# can.net
KiCad netlist of a schematic drawn in Altium Designer
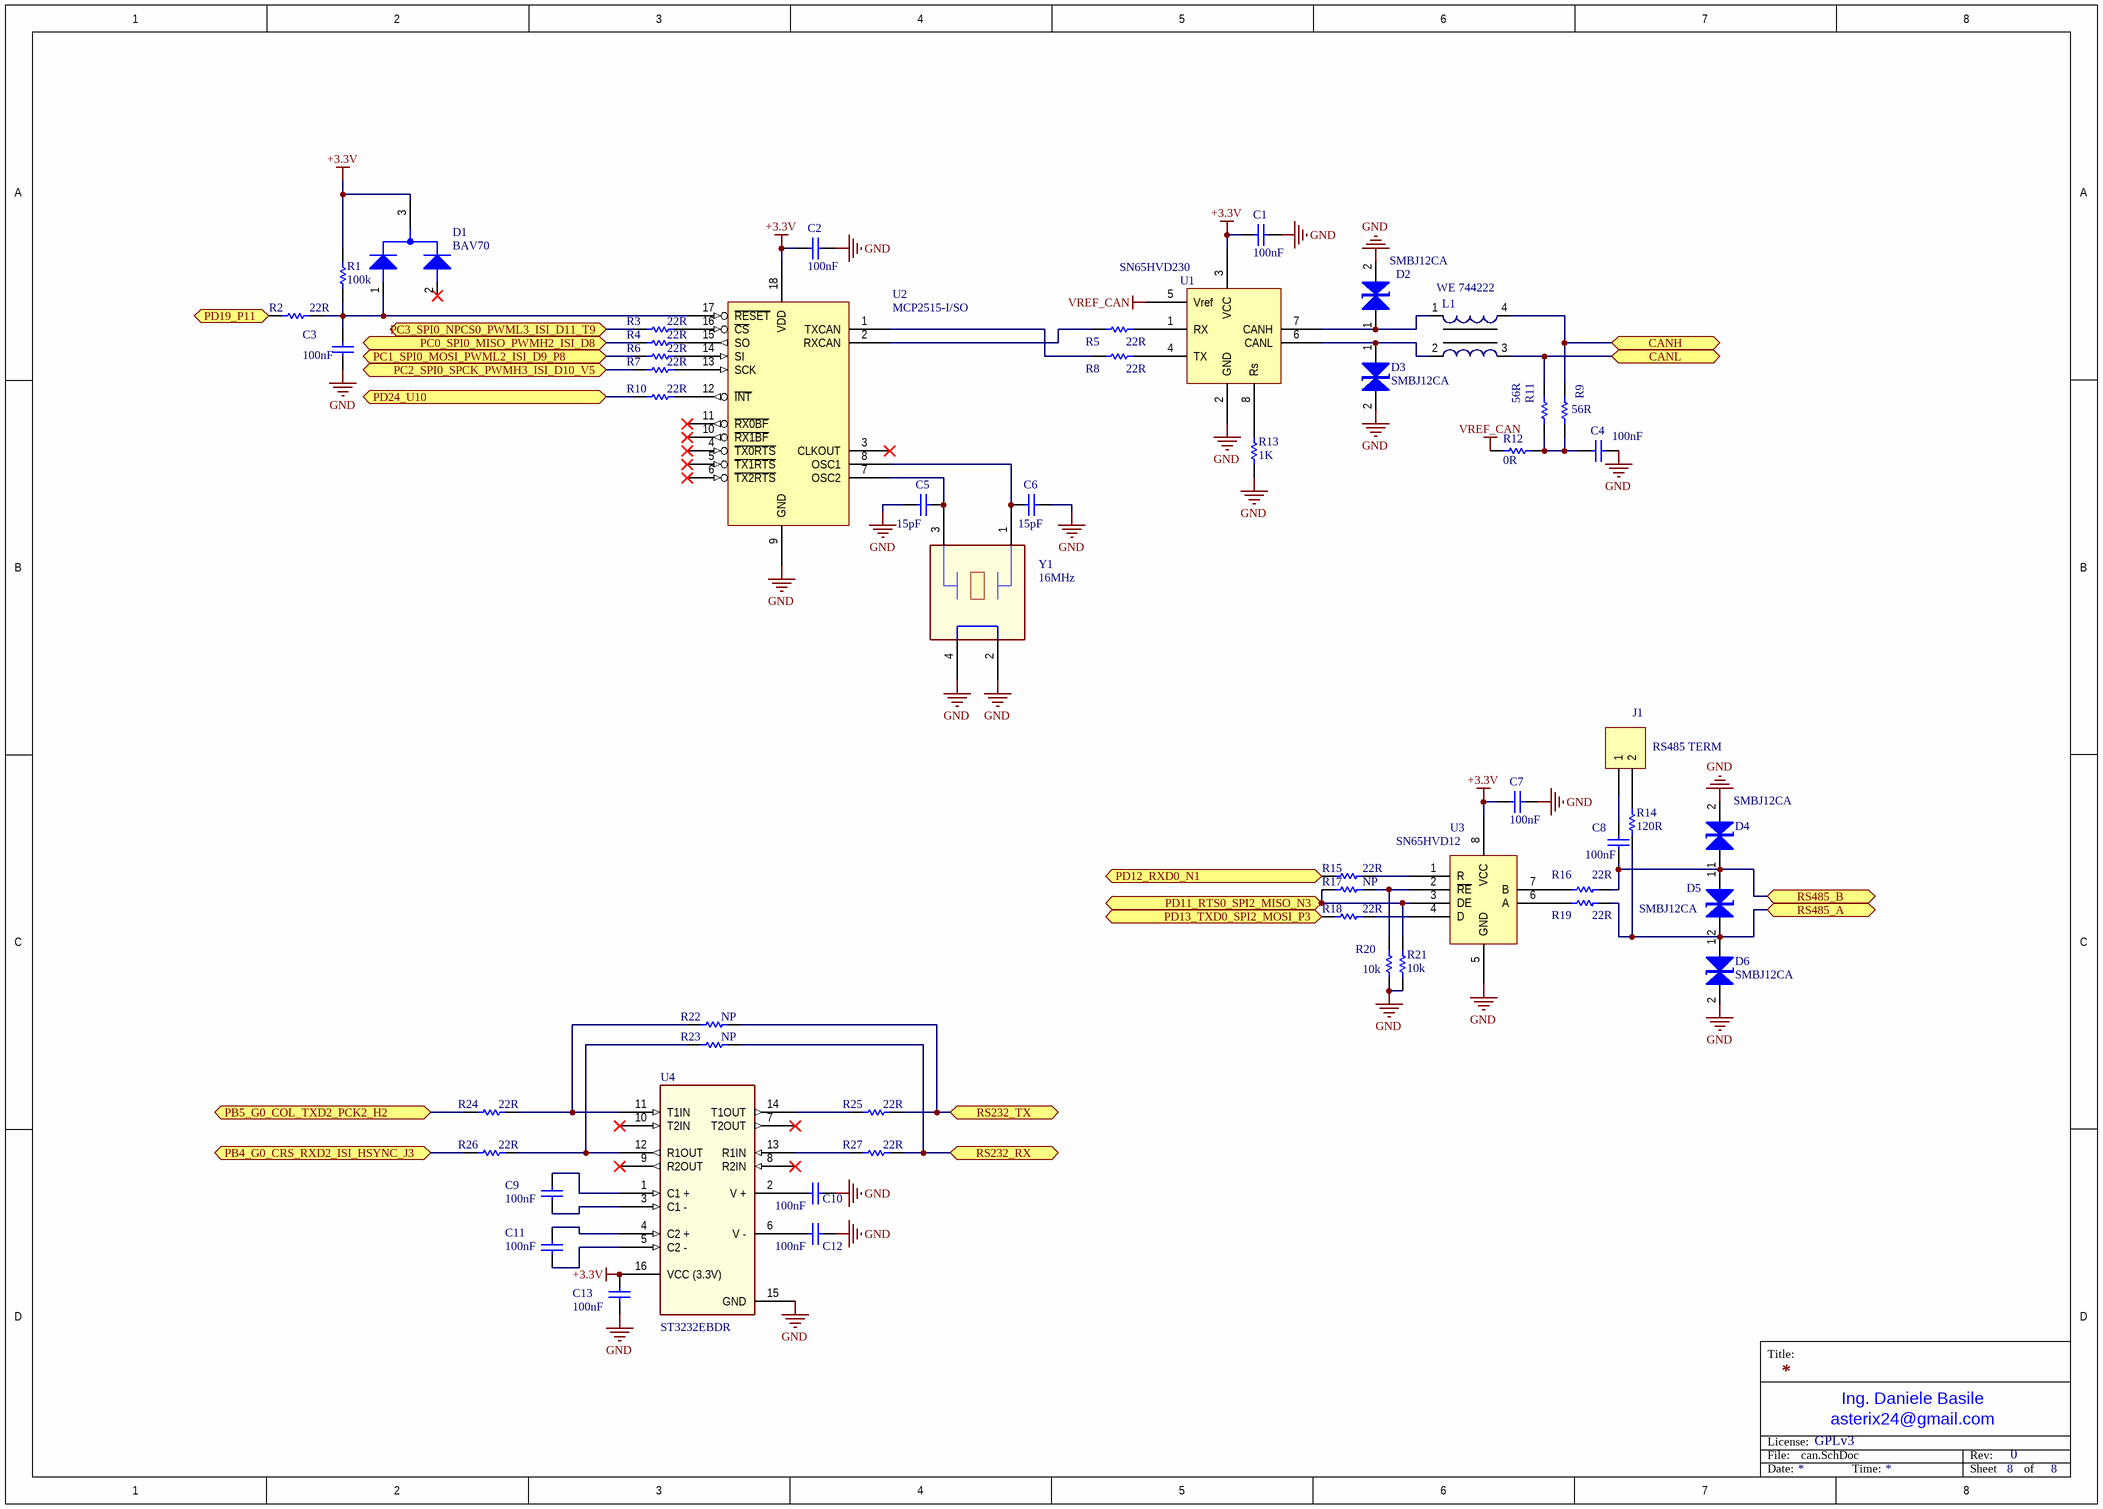
[diagram p0: can.SchDoc]

(export (version "E")
  (design (tool "Eeschema 10.0.6"))
  (components
    (comp (ref "C1")
      (value "100nF")
      (footprint "0603_[1608]")
      (description "Ceramic X7R 50V")
      (fields (field (name "PUBLISHER") "Altium Limited"))
      (libsource (lib "Miscellaneous Devices") (part "Cap"))
    )
    (comp (ref "C2")
      (value "100nF")
      (footprint "0603_[1608]")
      (description "Ceramic X7R 50V")
      (fields (field (name "PUBLISHER") "Altium Limited"))
      (libsource (lib "Miscellaneous Devices") (part "Cap"))
    )
    (comp (ref "C3")
      (value "100nF")
      (footprint "0603_[1608]")
      (description "Ceramic X7R 50V")
      (fields (field (name "PUBLISHER") "Altium Limited"))
      (libsource (lib "Miscellaneous Devices") (part "Cap"))
    )
    (comp (ref "C4")
      (value "100nF")
      (footprint "0603_[1608]")
      (description "Ceramic X7R 50V")
      (fields (field (name "PUBLISHER") "Altium Limited"))
      (libsource (lib "Miscellaneous Devices") (part "Cap"))
    )
    (comp (ref "C5")
      (value "15pF")
      (footprint "0603_[1608]")
      (description "Ceramic 50V NP0/C0G")
      (fields (field (name "PUBLISHER") "Altium Limited"))
      (libsource (lib "Miscellaneous Devices") (part "Cap"))
    )
    (comp (ref "C6")
      (value "15pF")
      (footprint "0603_[1608]")
      (description "Ceramic 50V NP0/C0G")
      (fields (field (name "PUBLISHER") "Altium Limited"))
      (libsource (lib "Miscellaneous Devices") (part "Cap"))
    )
    (comp (ref "C7")
      (value "100nF")
      (footprint "0603_[1608]")
      (description "Ceramic X7R 50V")
      (fields (field (name "PUBLISHER") "Altium Limited"))
      (libsource (lib "Miscellaneous Devices") (part "Cap"))
    )
    (comp (ref "C8")
      (value "100nF")
      (footprint "0603_[1608]")
      (description "Ceramic X7R 50V")
      (fields (field (name "PUBLISHER") "Altium Limited"))
      (libsource (lib "Miscellaneous Devices") (part "Cap"))
    )
    (comp (ref "C9")
      (value "100nF")
      (footprint "0603_[1608]")
      (description "Ceramic X7R 50V")
      (fields (field (name "PUBLISHER") "Altium Limited"))
      (libsource (lib "Miscellaneous Devices") (part "Cap"))
    )
    (comp (ref "C10")
      (value "100nF")
      (footprint "0603_[1608]")
      (description "Ceramic X7R 50V")
      (fields (field (name "PUBLISHER") "Altium Limited"))
      (libsource (lib "Miscellaneous Devices") (part "Cap"))
    )
    (comp (ref "C11")
      (value "100nF")
      (footprint "0603_[1608]")
      (description "Ceramic X7R 50V")
      (fields (field (name "PUBLISHER") "Altium Limited"))
      (libsource (lib "Miscellaneous Devices") (part "Cap"))
    )
    (comp (ref "C12")
      (value "100nF")
      (footprint "0603_[1608]")
      (description "Ceramic X7R 50V")
      (fields (field (name "PUBLISHER") "Altium Limited"))
      (libsource (lib "Miscellaneous Devices") (part "Cap"))
    )
    (comp (ref "C13")
      (value "100nF")
      (footprint "0603_[1608]")
      (description "Ceramic X7R 50V")
      (fields (field (name "PUBLISHER") "Altium Limited"))
      (libsource (lib "Miscellaneous Devices") (part "Cap"))
    )
    (comp (ref "D1")
      (value "BAV70")
      (footprint "SOT-23")
      (description "Diode")
      (libsource (lib "DEVELER_Library") (part "BAV70"))
    )
    (comp (ref "D2")
      (value "SMBJ12CA")
      (footprint "DO214AA_K1-A2_SMB")
      (description "TVS bidirectional")
      (libsource (lib "DEVELER_Library") (part "TVS bi"))
    )
    (comp (ref "D3")
      (value "SMBJ12CA")
      (footprint "DO214AA_K1-A2_SMB")
      (description "TVS bidirectional")
      (libsource (lib "DEVELER_Library") (part "TVS bi"))
    )
    (comp (ref "D4")
      (value "SMBJ12CA")
      (footprint "DO214AA_K1-A2_SMB")
      (description "TVS bidirectional")
      (libsource (lib "DEVELER_Library") (part "TVS bi"))
    )
    (comp (ref "D5")
      (value "SMBJ12CA")
      (footprint "DO214AA_K1-A2_SMB")
      (description "TVS bidirectional")
      (libsource (lib "DEVELER_Library") (part "TVS bi"))
    )
    (comp (ref "D6")
      (value "SMBJ12CA")
      (footprint "DO214AA_K1-A2_SMB")
      (description "TVS bidirectional")
      (libsource (lib "DEVELER_Library") (part "TVS bi"))
    )
    (comp (ref "J1")
      (value "RS485 TERM")
      (footprint "HEADER_1X2_2.54MM_THD")
      (description "Pin Header, 2.54mm, 1x2, 2pin")
      (fields (field (name "PUBLISHER") "Altium Limited"))
      (libsource (lib "Miscellaneous Connectors") (part "Header 2"))
    )
    (comp (ref "L1")
      (value "WE 744222")
      (footprint "WE-SL2")
      (description "Common Mode line Filter")
      (fields
        (field (name "PARTNO") "744821240")
        (field (name "MANUFACTURER") "Würth Elektronik eiSos GmbH")
        (field (name "CREATED BY") "Christin Zierenner")
      )
      (libsource (lib "DEVELER_Library") (part "WE-CMB XS, 744821240"))
    )
    (comp (ref "R1")
      (value "100k")
      (footprint "0603_[1608]")
      (description "Resistor")
      (libsource (lib "DEVELER_Library") (part "Res1"))
    )
    (comp (ref "R2")
      (value "22R")
      (footprint "0603_[1608]")
      (description "Resistor")
      (fields (field (name "PUBLISHER") "Altium Limited"))
      (libsource (lib "") (part "Res1_1"))
    )
    (comp (ref "R3")
      (value "22R")
      (footprint "0603_[1608]")
      (description "Resistor")
      (libsource (lib "DEVELER_Library") (part "Res1"))
    )
    (comp (ref "R4")
      (value "22R")
      (footprint "0603_[1608]")
      (description "Resistor")
      (libsource (lib "DEVELER_Library") (part "Res1"))
    )
    (comp (ref "R5")
      (value "22R")
      (footprint "0603_[1608]")
      (description "Resistor")
      (libsource (lib "DEVELER_Library") (part "Res1"))
    )
    (comp (ref "R6")
      (value "22R")
      (footprint "0603_[1608]")
      (description "Resistor")
      (libsource (lib "DEVELER_Library") (part "Res1"))
    )
    (comp (ref "R7")
      (value "22R")
      (footprint "0603_[1608]")
      (description "Resistor")
      (libsource (lib "DEVELER_Library") (part "Res1"))
    )
    (comp (ref "R8")
      (value "22R")
      (footprint "0603_[1608]")
      (description "Resistor")
      (libsource (lib "DEVELER_Library") (part "Res1"))
    )
    (comp (ref "R9")
      (value "56R")
      (footprint "0603_[1608]")
      (description "Resistor")
      (libsource (lib "DEVELER_Library") (part "Res1"))
    )
    (comp (ref "R10")
      (value "22R")
      (footprint "0603_[1608]")
      (description "Resistor")
      (libsource (lib "DEVELER_Library") (part "Res1"))
    )
    (comp (ref "R11")
      (value "56R")
      (footprint "0603_[1608]")
      (description "Resistor")
      (libsource (lib "DEVELER_Library") (part "Res1"))
    )
    (comp (ref "R12")
      (value "0R")
      (footprint "0603_[1608]")
      (description "Resistor")
      (libsource (lib "DEVELER_Library") (part "Res1"))
    )
    (comp (ref "R13")
      (value "1K")
      (footprint "0603_[1608]")
      (description "Resistor")
      (libsource (lib "DEVELER_Library") (part "Res1"))
    )
    (comp (ref "R14")
      (value "120R")
      (footprint "0603_[1608]")
      (description "Resistor")
      (libsource (lib "DEVELER_Library") (part "Res1"))
    )
    (comp (ref "R15")
      (value "22R")
      (footprint "0603_[1608]")
      (description "Resistor")
      (fields (field (name "PUBLISHER") "Altium Limited"))
      (libsource (lib "") (part "Res1_1"))
    )
    (comp (ref "R16")
      (value "22R")
      (footprint "0603_[1608]")
      (description "Resistor")
      (libsource (lib "DEVELER_Library") (part "Res1"))
    )
    (comp (ref "R17")
      (value "NP")
      (footprint "0603_[1608]")
      (description "Resistor")
      (libsource (lib "DEVELER_Library") (part "Res1"))
    )
    (comp (ref "R18")
      (value "22R")
      (footprint "0603_[1608]")
      (description "Resistor")
      (fields (field (name "PUBLISHER") "Altium Limited"))
      (libsource (lib "") (part "Res1_1"))
    )
    (comp (ref "R19")
      (value "22R")
      (footprint "0603_[1608]")
      (description "Resistor")
      (libsource (lib "DEVELER_Library") (part "Res1"))
    )
    (comp (ref "R20")
      (value "10k")
      (footprint "0603_[1608]")
      (description "Resistor")
      (libsource (lib "DEVELER_Library") (part "Res1"))
    )
    (comp (ref "R21")
      (value "10k")
      (footprint "0603_[1608]")
      (description "Resistor")
      (libsource (lib "DEVELER_Library") (part "Res1"))
    )
    (comp (ref "R22")
      (value "NP")
      (footprint "0603_[1608]")
      (description "Resistor")
      (libsource (lib "DEVELER_Library") (part "Res1"))
    )
    (comp (ref "R23")
      (value "NP")
      (footprint "0603_[1608]")
      (description "Resistor")
      (libsource (lib "DEVELER_Library") (part "Res1"))
    )
    (comp (ref "R24")
      (value "22R")
      (footprint "0603_[1608]")
      (description "Resistor")
      (libsource (lib "DEVELER_Library") (part "Res1"))
    )
    (comp (ref "R25")
      (value "22R")
      (footprint "0603_[1608]")
      (description "Resistor")
      (libsource (lib "DEVELER_Library") (part "Res1"))
    )
    (comp (ref "R26")
      (value "22R")
      (footprint "0603_[1608]")
      (description "Resistor")
      (libsource (lib "DEVELER_Library") (part "Res1"))
    )
    (comp (ref "R27")
      (value "22R")
      (footprint "0603_[1608]")
      (description "Resistor")
      (libsource (lib "DEVELER_Library") (part "Res1"))
    )
    (comp (ref "U1")
      (value "SN65HVD230")
      (footprint "SOIC8")
      (description "3.3V CAN bus transceiver (SN65HVD231; SN65HVD232)")
      (libsource (lib "DEVELER_Library") (part "SN65HVD230"))
    )
    (comp (ref "U2")
      (value "MCP2515-I/SO")
      (footprint "SOIC18")
      (description "Stand-Alone CAN controller with SPI interface")
      (libsource (lib "DEVELER_Library") (part "MCP2515"))
    )
    (comp (ref "U3")
      (value "SN65HVD12")
      (footprint "SOIC8")
      (description "3.3V to RS485 interface")
      (libsource (lib "DEVELER_Library") (part "SN65HVD12"))
    )
    (comp (ref "U4")
      (value "ST3232EBDR")
      (footprint "SOIC16")
      (description "3 to 5.5 V, low power, up to 400 kbps RS-232 driver")
      (fields (field (name "PART NUMBER") "STm ST3232CDR"))
      (libsource (lib "DEVELER_Library") (part "ST3232CDR"))
    )
    (comp (ref "Y1")
      (value "16MHz")
      (footprint "CRYSTAL_3.2X2.5MM_4P_SMD")
      (description "Crystal")
      (libsource (lib "DEVELER_Library") (part "CRYSTAL-4p"))
    )
  )
  (nets
    (net (code "1") (name "+3.3V") (class "Default")
      (node (ref "C1") (pin "2") (pinfunction "2_2") (pintype "passive"))
      (node (ref "C13") (pin "2") (pinfunction "2_2") (pintype "passive"))
      (node (ref "C2") (pin "2") (pinfunction "2_2") (pintype "passive"))
      (node (ref "C7") (pin "2") (pinfunction "2_2") (pintype "passive"))
      (node (ref "D1") (pin "3") (pinfunction "3_3") (pintype "passive"))
      (node (ref "R1") (pin "1") (pinfunction "1_1") (pintype "passive"))
      (node (ref "U1") (pin "3") (pinfunction "VCC_3") (pintype "power_in"))
      (node (ref "U2") (pin "18") (pinfunction "VDD_18") (pintype "power_in"))
      (node (ref "U3") (pin "8") (pinfunction "VCC_8") (pintype "power_in"))
      (node (ref "U4") (pin "16") (pinfunction "VCC_(3.3V)_16") (pintype "power_in"))
    )
    (net (code "2") (name "/CANH") (class "Default")
      (node (ref "L1") (pin "4") (pinfunction "4_4") (pintype "passive"))
      (node (ref "R9") (pin "1") (pinfunction "1_1") (pintype "passive"))
    )
    (net (code "3") (name "/CANL") (class "Default")
      (node (ref "L1") (pin "3") (pinfunction "3_3") (pintype "passive"))
      (node (ref "R11") (pin "1") (pinfunction "1_1") (pintype "passive"))
    )
    (net (code "4") (name "/PB4_G0_CRS_RXD2_ISI_HSYNC_J3") (class "Default")
      (node (ref "R26") (pin "1") (pinfunction "1_1") (pintype "passive"))
    )
    (net (code "5") (name "/PB5_G0_COL_TXD2_PCK2_H2") (class "Default")
      (node (ref "R24") (pin "1") (pinfunction "1_1") (pintype "passive"))
    )
    (net (code "6") (name "/PC0_SPI0_MISO_PWMH2_ISI_D8") (class "Default")
      (node (ref "R4") (pin "1") (pinfunction "1_1") (pintype "passive"))
    )
    (net (code "7") (name "/PC1_SPI0_MOSI_PWML2_ISI_D9_P8") (class "Default")
      (node (ref "R6") (pin "1") (pinfunction "1_1") (pintype "passive"))
    )
    (net (code "8") (name "/PC2_SPI0_SPCK_PWMH3_ISI_D10_V5") (class "Default")
      (node (ref "R7") (pin "1") (pinfunction "1_1") (pintype "passive"))
    )
    (net (code "9") (name "/PC3_SPI0_NPCS0_PWML3_ISI_D11_T9") (class "Default")
      (node (ref "R3") (pin "1") (pinfunction "1_1") (pintype "passive"))
    )
    (net (code "10") (name "/PD11_RTS0_SPI2_MISO_N3") (class "Default")
      (node (ref "R17") (pin "2") (pinfunction "2_2") (pintype "passive"))
      (node (ref "R21") (pin "2") (pinfunction "2_2") (pintype "passive"))
      (node (ref "U3") (pin "3") (pinfunction "DE_3") (pintype "passive"))
    )
    (net (code "11") (name "/PD12_RXD0_N1") (class "Default")
      (node (ref "R15") (pin "2") (pinfunction "2_2") (pintype "passive"))
    )
    (net (code "12") (name "/PD13_TXD0_SPI2_MOSI_P3") (class "Default")
      (node (ref "R18") (pin "2") (pinfunction "2_2") (pintype "passive"))
    )
    (net (code "13") (name "/PD19_P11") (class "Default")
      (node (ref "R2") (pin "2") (pinfunction "2_2") (pintype "passive"))
    )
    (net (code "14") (name "/PD24_U10") (class "Default")
      (node (ref "R10") (pin "1") (pinfunction "1_1") (pintype "passive"))
    )
    (net (code "15") (name "/RS232_RX") (class "Default")
      (node (ref "R23") (pin "2") (pinfunction "2_2") (pintype "passive"))
      (node (ref "R27") (pin "2") (pinfunction "2_2") (pintype "passive"))
    )
    (net (code "16") (name "/RS232_TX") (class "Default")
      (node (ref "R22") (pin "2") (pinfunction "2_2") (pintype "passive"))
      (node (ref "R25") (pin "2") (pinfunction "2_2") (pintype "passive"))
    )
    (net (code "17") (name "/RS485_A") (class "Default")
      (node (ref "D5") (pin "2") (pinfunction "2_2") (pintype "passive"))
      (node (ref "D6") (pin "1") (pinfunction "1_1") (pintype "passive"))
      (node (ref "R14") (pin "2") (pinfunction "2_2") (pintype "passive"))
      (node (ref "R19") (pin "2") (pinfunction "2_2") (pintype "passive"))
    )
    (net (code "18") (name "/RS485_B") (class "Default")
      (node (ref "C8") (pin "2") (pinfunction "2_2") (pintype "passive"))
      (node (ref "D4") (pin "1") (pinfunction "1_1") (pintype "passive"))
      (node (ref "D5") (pin "1") (pinfunction "1_1") (pintype "passive"))
      (node (ref "R16") (pin "2") (pinfunction "2_2") (pintype "passive"))
    )
    (net (code "19") (name "GND") (class "Default")
      (node (ref "C1") (pin "1") (pinfunction "1_1") (pintype "passive"))
      (node (ref "C10") (pin "1") (pinfunction "1_1") (pintype "passive"))
      (node (ref "C12") (pin "1") (pinfunction "1_1") (pintype "passive"))
      (node (ref "C13") (pin "1") (pinfunction "1_1") (pintype "passive"))
      (node (ref "C2") (pin "1") (pinfunction "1_1") (pintype "passive"))
      (node (ref "C3") (pin "2") (pinfunction "2_2") (pintype "passive"))
      (node (ref "C4") (pin "1") (pinfunction "1_1") (pintype "passive"))
      (node (ref "C5") (pin "2") (pinfunction "2_2") (pintype "passive"))
      (node (ref "C6") (pin "1") (pinfunction "1_1") (pintype "passive"))
      (node (ref "C7") (pin "1") (pinfunction "1_1") (pintype "passive"))
      (node (ref "D2") (pin "2") (pinfunction "2_2") (pintype "passive"))
      (node (ref "D3") (pin "2") (pinfunction "2_2") (pintype "passive"))
      (node (ref "D4") (pin "2") (pinfunction "2_2") (pintype "passive"))
      (node (ref "D6") (pin "2") (pinfunction "2_2") (pintype "passive"))
      (node (ref "R13") (pin "1") (pinfunction "1_1") (pintype "passive"))
      (node (ref "R20") (pin "1") (pinfunction "1_1") (pintype "passive"))
      (node (ref "R21") (pin "1") (pinfunction "1_1") (pintype "passive"))
      (node (ref "U1") (pin "2") (pinfunction "GND_2") (pintype "power_in"))
      (node (ref "U2") (pin "9") (pinfunction "GND_9") (pintype "power_in"))
      (node (ref "U3") (pin "5") (pinfunction "GND_5") (pintype "power_in"))
      (node (ref "U4") (pin "15") (pinfunction "GND_15") (pintype "power_in"))
      (node (ref "Y1") (pin "2") (pinfunction "2_2") (pintype "passive"))
      (node (ref "Y1") (pin "4") (pinfunction "4_4") (pintype "passive"))
    )
    (net (code "20") (name "Net-(C4-Pad2)") (class "Default")
      (node (ref "C4") (pin "2") (pinfunction "2_2") (pintype "passive"))
      (node (ref "R11") (pin "2") (pinfunction "2_2") (pintype "passive"))
      (node (ref "R12") (pin "2") (pinfunction "2_2") (pintype "passive"))
      (node (ref "R9") (pin "2") (pinfunction "2_2") (pintype "passive"))
    )
    (net (code "21") (name "Net-(C8-Pad1)") (class "Default")
      (node (ref "C8") (pin "1") (pinfunction "1_1") (pintype "passive"))
      (node (ref "J1") (pin "1") (pinfunction "1_1") (pintype "passive"))
    )
    (net (code "22") (name "Net-(J1-Pad2)") (class "Default")
      (node (ref "J1") (pin "2") (pinfunction "2_2") (pintype "passive"))
      (node (ref "R14") (pin "1") (pinfunction "1_1") (pintype "passive"))
    )
    (net (code "23") (name "Net-(U1-CANH)") (class "Default")
      (node (ref "D2") (pin "1") (pinfunction "1_1") (pintype "passive"))
      (node (ref "L1") (pin "1") (pinfunction "1_1") (pintype "passive"))
      (node (ref "U1") (pin "7") (pinfunction "CANH_7") (pintype "passive"))
    )
    (net (code "24") (name "Net-(U1-CANL)") (class "Default")
      (node (ref "D3") (pin "1") (pinfunction "1_1") (pintype "passive"))
      (node (ref "L1") (pin "2") (pinfunction "2_2") (pintype "passive"))
      (node (ref "U1") (pin "6") (pinfunction "CANL_6") (pintype "passive"))
    )
    (net (code "25") (name "Net-(U1-RX)") (class "Default")
      (node (ref "R5") (pin "2") (pinfunction "2_2") (pintype "passive"))
      (node (ref "U1") (pin "1") (pinfunction "RX_1") (pintype "passive"))
    )
    (net (code "26") (name "Net-(U1-Rs)") (class "Default")
      (node (ref "R13") (pin "2") (pinfunction "2_2") (pintype "passive"))
      (node (ref "U1") (pin "8") (pinfunction "Rs_8") (pintype "passive"))
    )
    (net (code "27") (name "Net-(U1-TX)") (class "Default")
      (node (ref "R8") (pin "2") (pinfunction "2_2") (pintype "passive"))
      (node (ref "U1") (pin "4") (pinfunction "TX_4") (pintype "passive"))
    )
    (net (code "28") (name "Net-(U2-OSC1)") (class "Default")
      (node (ref "C6") (pin "2") (pinfunction "2_2") (pintype "passive"))
      (node (ref "U2") (pin "8") (pinfunction "OSC1_8") (pintype "passive"))
      (node (ref "Y1") (pin "1") (pinfunction "1_1") (pintype "passive"))
    )
    (net (code "29") (name "Net-(U2-OSC2)") (class "Default")
      (node (ref "C5") (pin "1") (pinfunction "1_1") (pintype "passive"))
      (node (ref "U2") (pin "7") (pinfunction "OSC2_7") (pintype "passive"))
      (node (ref "Y1") (pin "3") (pinfunction "3_3") (pintype "passive"))
    )
    (net (code "30") (name "Net-(U2-RXCAN)") (class "Default")
      (node (ref "R5") (pin "1") (pinfunction "1_1") (pintype "passive"))
      (node (ref "U2") (pin "2") (pinfunction "RXCAN_2") (pintype "passive"))
    )
    (net (code "31") (name "Net-(U2-SCK)") (class "Default")
      (node (ref "R7") (pin "2") (pinfunction "2_2") (pintype "passive"))
      (node (ref "U2") (pin "13") (pinfunction "SCK_13") (pintype "input"))
    )
    (net (code "32") (name "Net-(U2-SI)") (class "Default")
      (node (ref "R6") (pin "2") (pinfunction "2_2") (pintype "passive"))
      (node (ref "U2") (pin "14") (pinfunction "SI_14") (pintype "input"))
    )
    (net (code "33") (name "Net-(U2-SO)") (class "Default")
      (node (ref "R4") (pin "2") (pinfunction "2_2") (pintype "passive"))
      (node (ref "U2") (pin "15") (pinfunction "SO_15") (pintype "output"))
    )
    (net (code "34") (name "Net-(U2-TXCAN)") (class "Default")
      (node (ref "R8") (pin "1") (pinfunction "1_1") (pintype "passive"))
      (node (ref "U2") (pin "1") (pinfunction "TXCAN_1") (pintype "passive"))
    )
    (net (code "35") (name "Net-(U2-~{CS})") (class "Default")
      (node (ref "R3") (pin "2") (pinfunction "2_2") (pintype "passive"))
      (node (ref "U2") (pin "16") (pinfunction "~{CS}_16") (pintype "input"))
    )
    (net (code "36") (name "Net-(U2-~{INT})") (class "Default")
      (node (ref "R10") (pin "2") (pinfunction "2_2") (pintype "passive"))
      (node (ref "U2") (pin "12") (pinfunction "~{INT}_12") (pintype "output"))
    )
    (net (code "37") (name "Net-(U2-~{RESET})") (class "Default")
      (node (ref "C3") (pin "1") (pinfunction "1_1") (pintype "passive"))
      (node (ref "D1") (pin "1") (pinfunction "1_1") (pintype "passive"))
      (node (ref "R1") (pin "2") (pinfunction "2_2") (pintype "passive"))
      (node (ref "R2") (pin "1") (pinfunction "1_1") (pintype "passive"))
      (node (ref "U2") (pin "17") (pinfunction "~{RESET}_17") (pintype "input"))
    )
    (net (code "38") (name "Net-(U3-A)") (class "Default")
      (node (ref "R19") (pin "1") (pinfunction "1_1") (pintype "passive"))
      (node (ref "U3") (pin "6") (pinfunction "A_6") (pintype "passive"))
    )
    (net (code "39") (name "Net-(U3-B)") (class "Default")
      (node (ref "R16") (pin "1") (pinfunction "1_1") (pintype "passive"))
      (node (ref "U3") (pin "7") (pinfunction "B_7") (pintype "passive"))
    )
    (net (code "40") (name "Net-(U3-D)") (class "Default")
      (node (ref "R18") (pin "1") (pinfunction "1_1") (pintype "passive"))
      (node (ref "U3") (pin "4") (pinfunction "D_4") (pintype "passive"))
    )
    (net (code "41") (name "Net-(U3-R)") (class "Default")
      (node (ref "R15") (pin "1") (pinfunction "1_1") (pintype "passive"))
      (node (ref "U3") (pin "1") (pinfunction "R_1") (pintype "passive"))
    )
    (net (code "42") (name "Net-(U3-~{RE})") (class "Default")
      (node (ref "R17") (pin "1") (pinfunction "1_1") (pintype "passive"))
      (node (ref "R20") (pin "2") (pinfunction "2_2") (pintype "passive"))
      (node (ref "U3") (pin "2") (pinfunction "~{RE}_2") (pintype "passive"))
    )
    (net (code "43") (name "Net-(U4-C1_+)") (class "Default")
      (node (ref "C9") (pin "1") (pinfunction "1_1") (pintype "passive"))
      (node (ref "U4") (pin "1") (pinfunction "C1_+_1") (pintype "input"))
    )
    (net (code "44") (name "Net-(U4-C1_-)") (class "Default")
      (node (ref "C9") (pin "2") (pinfunction "2_2") (pintype "passive"))
      (node (ref "U4") (pin "3") (pinfunction "C1_-_3") (pintype "input"))
    )
    (net (code "45") (name "Net-(U4-C2_+)") (class "Default")
      (node (ref "C11") (pin "2") (pinfunction "2_2") (pintype "passive"))
      (node (ref "U4") (pin "4") (pinfunction "C2_+_4") (pintype "input"))
    )
    (net (code "46") (name "Net-(U4-C2_-)") (class "Default")
      (node (ref "C11") (pin "1") (pinfunction "1_1") (pintype "passive"))
      (node (ref "U4") (pin "5") (pinfunction "C2_-_5") (pintype "input"))
    )
    (net (code "47") (name "Net-(U4-R1IN)") (class "Default")
      (node (ref "R27") (pin "1") (pinfunction "1_1") (pintype "passive"))
      (node (ref "U4") (pin "13") (pinfunction "R1IN_13") (pintype "input"))
    )
    (net (code "48") (name "Net-(U4-R1OUT)") (class "Default")
      (node (ref "R23") (pin "1") (pinfunction "1_1") (pintype "passive"))
      (node (ref "R26") (pin "2") (pinfunction "2_2") (pintype "passive"))
      (node (ref "U4") (pin "12") (pinfunction "R1OUT_12") (pintype "output"))
    )
    (net (code "49") (name "Net-(U4-T1IN)") (class "Default")
      (node (ref "R22") (pin "1") (pinfunction "1_1") (pintype "passive"))
      (node (ref "R24") (pin "2") (pinfunction "2_2") (pintype "passive"))
      (node (ref "U4") (pin "11") (pinfunction "T1IN_11") (pintype "input"))
    )
    (net (code "50") (name "Net-(U4-T1OUT)") (class "Default")
      (node (ref "R25") (pin "1") (pinfunction "1_1") (pintype "passive"))
      (node (ref "U4") (pin "14") (pinfunction "T1OUT_14") (pintype "output"))
    )
    (net (code "51") (name "Net-(U4-V_+)") (class "Default")
      (node (ref "C10") (pin "2") (pinfunction "2_2") (pintype "passive"))
      (node (ref "U4") (pin "2") (pinfunction "V_+_2") (pintype "power_in"))
    )
    (net (code "52") (name "Net-(U4-V_-)") (class "Default")
      (node (ref "C12") (pin "2") (pinfunction "2_2") (pintype "passive"))
      (node (ref "U4") (pin "6") (pinfunction "V_-_6") (pintype "power_in"))
    )
    (net (code "53") (name "VREF_CAN") (class "Default")
      (node (ref "R12") (pin "1") (pinfunction "1_1") (pintype "passive"))
      (node (ref "U1") (pin "5") (pinfunction "Vref_5") (pintype "passive"))
    )
    (net (code "54") (name "unconnected-(D1-Pad2)") (class "Default")
      (node (ref "D1") (pin "2") (pinfunction "2_2") (pintype "passive+no_connect"))
    )
    (net (code "55") (name "unconnected-(U2-CLKOUT-Pad3)") (class "Default")
      (node (ref "U2") (pin "3") (pinfunction "CLKOUT_3") (pintype "passive+no_connect"))
    )
    (net (code "56") (name "unconnected-(U2-~{RX0BF}-Pad11)") (class "Default")
      (node (ref "U2") (pin "11") (pinfunction "~{RX0BF}_11") (pintype "output+no_connect"))
    )
    (net (code "57") (name "unconnected-(U2-~{RX1BF}-Pad10)") (class "Default")
      (node (ref "U2") (pin "10") (pinfunction "~{RX1BF}_10") (pintype "output+no_connect"))
    )
    (net (code "58") (name "unconnected-(U2-~{TX0RTS}-Pad4)") (class "Default")
      (node (ref "U2") (pin "4") (pinfunction "~{TX0RTS}_4") (pintype "input+no_connect"))
    )
    (net (code "59") (name "unconnected-(U2-~{TX1RTS}-Pad5)") (class "Default")
      (node (ref "U2") (pin "5") (pinfunction "~{TX1RTS}_5") (pintype "input+no_connect"))
    )
    (net (code "60") (name "unconnected-(U2-~{TX2RTS}-Pad6)") (class "Default")
      (node (ref "U2") (pin "6") (pinfunction "~{TX2RTS}_6") (pintype "input+no_connect"))
    )
    (net (code "61") (name "unconnected-(U4-R2IN-Pad8)") (class "Default")
      (node (ref "U4") (pin "8") (pinfunction "R2IN_8") (pintype "input+no_connect"))
    )
    (net (code "62") (name "unconnected-(U4-R2OUT-Pad9)") (class "Default")
      (node (ref "U4") (pin "9") (pinfunction "R2OUT_9") (pintype "output+no_connect"))
    )
    (net (code "63") (name "unconnected-(U4-T2IN-Pad10)") (class "Default")
      (node (ref "U4") (pin "10") (pinfunction "T2IN_10") (pintype "input+no_connect"))
    )
    (net (code "64") (name "unconnected-(U4-T2OUT-Pad7)") (class "Default")
      (node (ref "U4") (pin "7") (pinfunction "T2OUT_7") (pintype "output+no_connect"))
    )
  )
)
